# extio.net
KiCad netlist of a schematic drawn in EAGLE
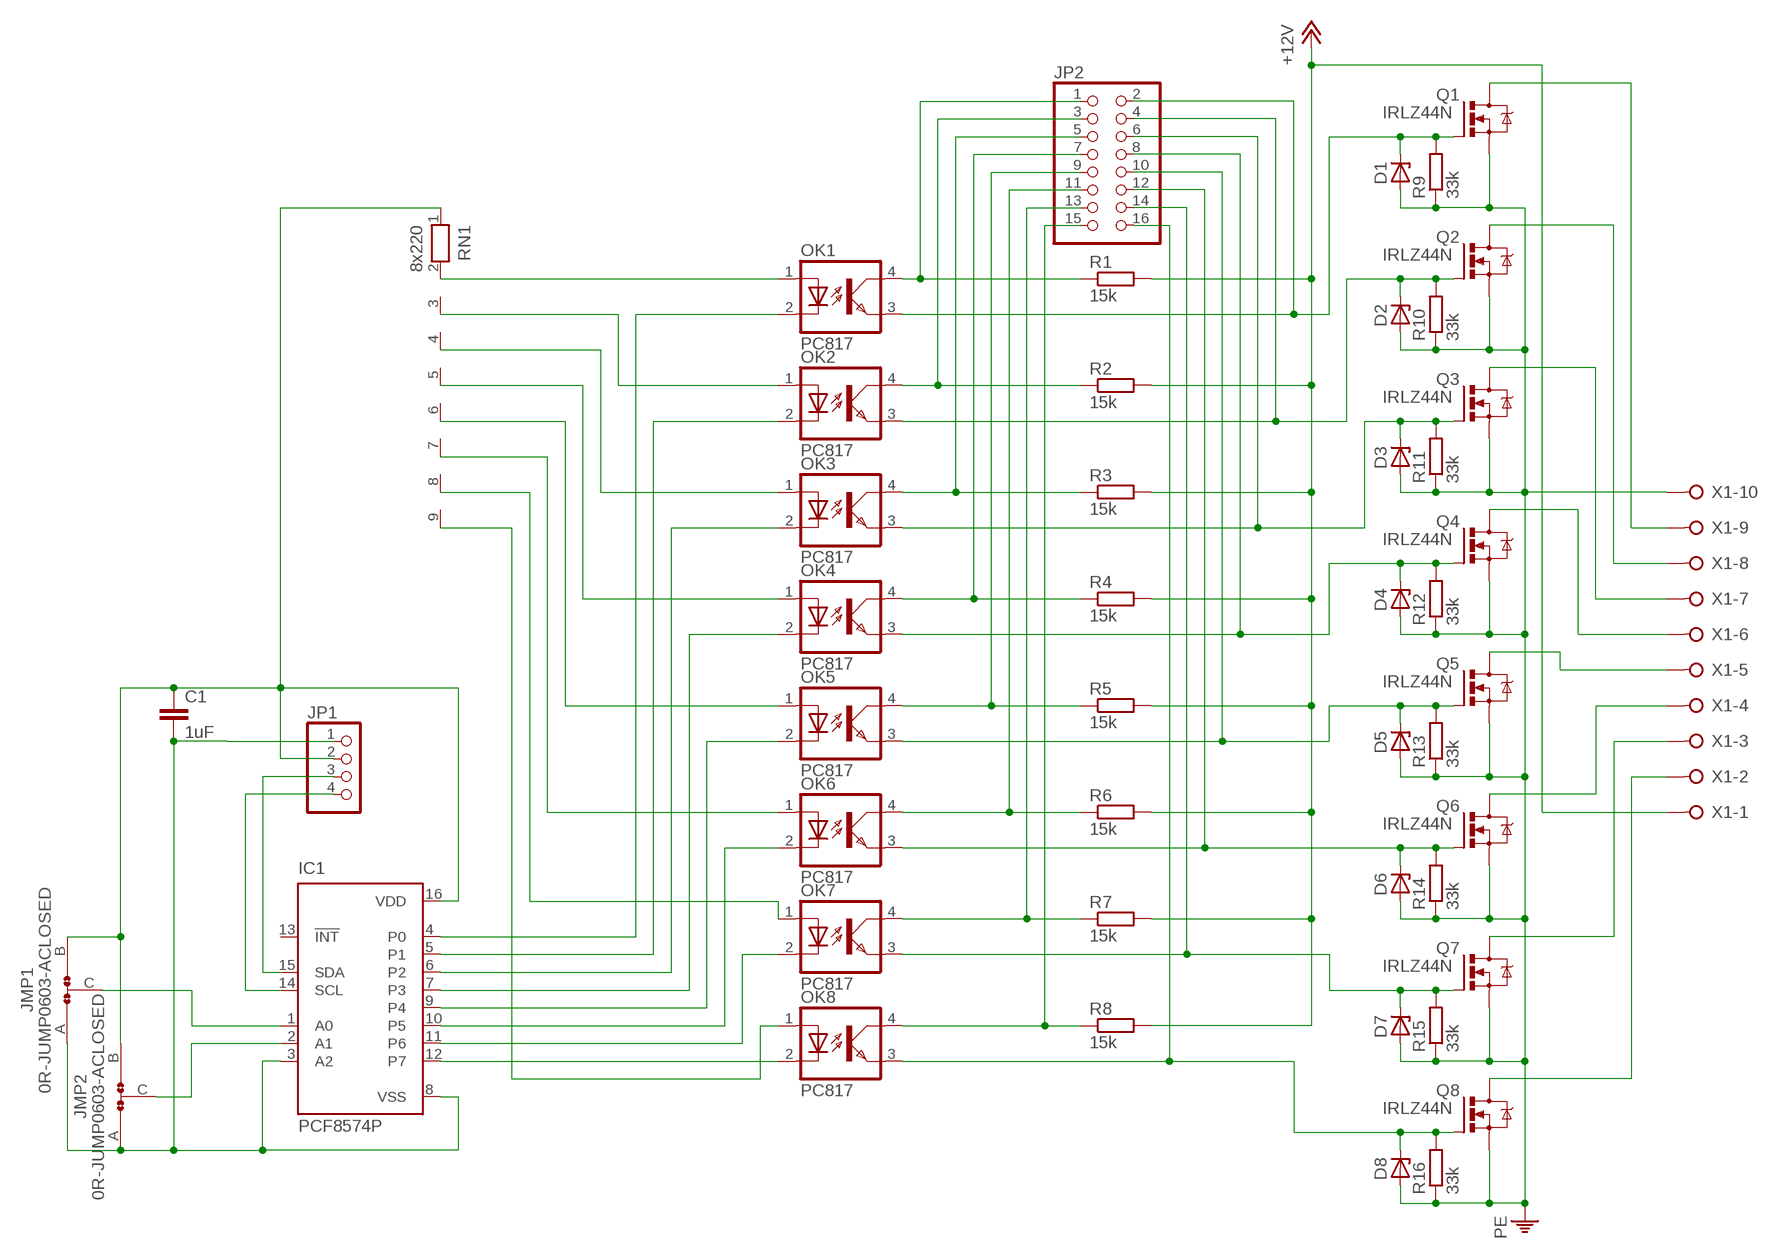
[diagram p0: schematic, sheet 1]

(export (version "E")
  (design (tool "Eeschema 10.0.6"))
  (components
    (comp (ref "C1")
      (value "1uF")
      (footprint "eagle-import:C0603")
      (libsource (lib "eagle-import") (part "C-EUC0603"))
    )
    (comp (ref "D1")
      (value "ZENER-DIODESOD80C")
      (footprint "eagle-import:SOD80C")
      (libsource (lib "eagle-import") (part "ZENER-DIODESOD80C"))
    )
    (comp (ref "D2")
      (value "ZENER-DIODESOD80C")
      (footprint "eagle-import:SOD80C")
      (libsource (lib "eagle-import") (part "ZENER-DIODESOD80C"))
    )
    (comp (ref "D3")
      (value "ZENER-DIODESOD80C")
      (footprint "eagle-import:SOD80C")
      (libsource (lib "eagle-import") (part "ZENER-DIODESOD80C"))
    )
    (comp (ref "D4")
      (value "ZENER-DIODESOD80C")
      (footprint "eagle-import:SOD80C")
      (libsource (lib "eagle-import") (part "ZENER-DIODESOD80C"))
    )
    (comp (ref "D5")
      (value "ZENER-DIODESOD80C")
      (footprint "eagle-import:SOD80C")
      (libsource (lib "eagle-import") (part "ZENER-DIODESOD80C"))
    )
    (comp (ref "D6")
      (value "ZENER-DIODESOD80C")
      (footprint "eagle-import:SOD80C")
      (libsource (lib "eagle-import") (part "ZENER-DIODESOD80C"))
    )
    (comp (ref "D7")
      (value "ZENER-DIODESOD80C")
      (footprint "eagle-import:SOD80C")
      (libsource (lib "eagle-import") (part "ZENER-DIODESOD80C"))
    )
    (comp (ref "D8")
      (value "ZENER-DIODESOD80C")
      (footprint "eagle-import:SOD80C")
      (libsource (lib "eagle-import") (part "ZENER-DIODESOD80C"))
    )
    (comp (ref "IC1")
      (value "PCF8574P")
      (footprint "eagle-import:DIL16")
      (fields (field (name "MPN") "PCF8574PN"))
      (libsource (lib "eagle-import") (part "PCF8574P"))
    )
    (comp (ref "JMP1")
      (value "0R-JUMP0603-ACLOSED")
      (footprint "eagle-import:JMP0603-ACLOSED")
      (libsource (lib "eagle-import") (part "0R-JUMP0603-ACLOSED"))
    )
    (comp (ref "JMP2")
      (value "0R-JUMP0603-ACLOSED")
      (footprint "eagle-import:JMP0603-ACLOSED")
      (libsource (lib "eagle-import") (part "0R-JUMP0603-ACLOSED"))
    )
    (comp (ref "JP1")
      (value "PINHD-1X4")
      (footprint "eagle-import:1X04")
      (libsource (lib "eagle-import") (part "PINHD-1X4"))
    )
    (comp (ref "JP2")
      (value "PINHD-2X8")
      (footprint "eagle-import:2X08")
      (libsource (lib "eagle-import") (part "PINHD-2X8"))
    )
    (comp (ref "OK1")
      (value "PC817")
      (footprint "eagle-import:DIL04")
      (fields (field (name "MPN") "PC817X4J000F"))
      (libsource (lib "eagle-import") (part "PC817"))
    )
    (comp (ref "OK2")
      (value "PC817")
      (footprint "eagle-import:DIL04")
      (fields (field (name "MPN") "PC817X4J000F"))
      (libsource (lib "eagle-import") (part "PC817"))
    )
    (comp (ref "OK3")
      (value "PC817")
      (footprint "eagle-import:DIL04")
      (fields (field (name "MPN") "PC817X4J000F"))
      (libsource (lib "eagle-import") (part "PC817"))
    )
    (comp (ref "OK4")
      (value "PC817")
      (footprint "eagle-import:DIL04")
      (fields (field (name "MPN") "PC817X4J000F"))
      (libsource (lib "eagle-import") (part "PC817"))
    )
    (comp (ref "OK5")
      (value "PC817")
      (footprint "eagle-import:DIL04")
      (fields (field (name "MPN") "PC817X4J000F"))
      (libsource (lib "eagle-import") (part "PC817"))
    )
    (comp (ref "OK6")
      (value "PC817")
      (footprint "eagle-import:DIL04")
      (fields (field (name "MPN") "PC817X4J000F"))
      (libsource (lib "eagle-import") (part "PC817"))
    )
    (comp (ref "OK7")
      (value "PC817")
      (footprint "eagle-import:DIL04")
      (fields (field (name "MPN") "PC817X4J000F"))
      (libsource (lib "eagle-import") (part "PC817"))
    )
    (comp (ref "OK8")
      (value "PC817")
      (footprint "eagle-import:DIL04")
      (fields (field (name "MPN") "PC817X4J000F"))
      (libsource (lib "eagle-import") (part "PC817"))
    )
    (comp (ref "Q1")
      (value "IRLZ44N")
      (footprint "eagle-import:TO220V")
      (libsource (lib "eagle-import") (part "IRLZ44N"))
    )
    (comp (ref "Q2")
      (value "IRLZ44N")
      (footprint "eagle-import:TO220V")
      (libsource (lib "eagle-import") (part "IRLZ44N"))
    )
    (comp (ref "Q3")
      (value "IRLZ44N")
      (footprint "eagle-import:TO220V")
      (libsource (lib "eagle-import") (part "IRLZ44N"))
    )
    (comp (ref "Q4")
      (value "IRLZ44N")
      (footprint "eagle-import:TO220V")
      (libsource (lib "eagle-import") (part "IRLZ44N"))
    )
    (comp (ref "Q5")
      (value "IRLZ44N")
      (footprint "eagle-import:TO220V")
      (libsource (lib "eagle-import") (part "IRLZ44N"))
    )
    (comp (ref "Q6")
      (value "IRLZ44N")
      (footprint "eagle-import:TO220V")
      (libsource (lib "eagle-import") (part "IRLZ44N"))
    )
    (comp (ref "Q7")
      (value "IRLZ44N")
      (footprint "eagle-import:TO220V")
      (libsource (lib "eagle-import") (part "IRLZ44N"))
    )
    (comp (ref "Q8")
      (value "IRLZ44N")
      (footprint "eagle-import:TO220V")
      (libsource (lib "eagle-import") (part "IRLZ44N"))
    )
    (comp (ref "R1")
      (value "15k")
      (footprint "eagle-import:R0603")
      (libsource (lib "eagle-import") (part "R-EU_R0603"))
    )
    (comp (ref "R2")
      (value "15k")
      (footprint "eagle-import:R0603")
      (libsource (lib "eagle-import") (part "R-EU_R0603"))
    )
    (comp (ref "R3")
      (value "15k")
      (footprint "eagle-import:R0603")
      (libsource (lib "eagle-import") (part "R-EU_R0603"))
    )
    (comp (ref "R4")
      (value "15k")
      (footprint "eagle-import:R0603")
      (libsource (lib "eagle-import") (part "R-EU_R0603"))
    )
    (comp (ref "R5")
      (value "15k")
      (footprint "eagle-import:R0603")
      (libsource (lib "eagle-import") (part "R-EU_R0603"))
    )
    (comp (ref "R6")
      (value "15k")
      (footprint "eagle-import:R0603")
      (libsource (lib "eagle-import") (part "R-EU_R0603"))
    )
    (comp (ref "R7")
      (value "15k")
      (footprint "eagle-import:R0603")
      (libsource (lib "eagle-import") (part "R-EU_R0603"))
    )
    (comp (ref "R8")
      (value "15k")
      (footprint "eagle-import:R0603")
      (libsource (lib "eagle-import") (part "R-EU_R0603"))
    )
    (comp (ref "R9")
      (value "33k")
      (footprint "eagle-import:R0603")
      (libsource (lib "eagle-import") (part "R-EU_R0603"))
    )
    (comp (ref "R10")
      (value "33k")
      (footprint "eagle-import:R0603")
      (libsource (lib "eagle-import") (part "R-EU_R0603"))
    )
    (comp (ref "R11")
      (value "33k")
      (footprint "eagle-import:R0603")
      (libsource (lib "eagle-import") (part "R-EU_R0603"))
    )
    (comp (ref "R12")
      (value "33k")
      (footprint "eagle-import:R0603")
      (libsource (lib "eagle-import") (part "R-EU_R0603"))
    )
    (comp (ref "R13")
      (value "33k")
      (footprint "eagle-import:R0603")
      (libsource (lib "eagle-import") (part "R-EU_R0603"))
    )
    (comp (ref "R14")
      (value "33k")
      (footprint "eagle-import:R0603")
      (libsource (lib "eagle-import") (part "R-EU_R0603"))
    )
    (comp (ref "R15")
      (value "33k")
      (footprint "eagle-import:R0603")
      (libsource (lib "eagle-import") (part "R-EU_R0603"))
    )
    (comp (ref "R16")
      (value "33k")
      (footprint "eagle-import:R0603")
      (libsource (lib "eagle-import") (part "R-EU_R0603"))
    )
    (comp (ref "RN1")
      (value "8x220")
      (footprint "eagle-import:RN-9")
      (libsource (lib "eagle-import") (part "RN08"))
    )
    (comp (ref "X1")
      (value "W237-10P")
      (footprint "eagle-import:W237-10P")
      (libsource (lib "eagle-import") (part "W237-10P"))
    )
  )
  (nets
    (net (code "1") (name "+12V") (class "Default")
      (node (ref "R1") (pin "2") (pinfunction "2_2") (pintype "passive"))
      (node (ref "R2") (pin "2") (pinfunction "2_2") (pintype "passive"))
      (node (ref "R3") (pin "2") (pinfunction "2_2") (pintype "passive"))
      (node (ref "R4") (pin "2") (pinfunction "2_2") (pintype "passive"))
      (node (ref "R5") (pin "2") (pinfunction "2_2") (pintype "passive"))
      (node (ref "R6") (pin "2") (pinfunction "2_2") (pintype "passive"))
      (node (ref "R7") (pin "2") (pinfunction "2_2") (pintype "passive"))
      (node (ref "R8") (pin "2") (pinfunction "2_2") (pintype "passive"))
      (node (ref "X1") (pin "1") (pinfunction "KL_1") (pintype "passive"))
    )
    (net (code "2") (name "Net-(IC1-A0)") (class "Default")
      (node (ref "IC1") (pin "1") (pinfunction "A0_1") (pintype "input"))
      (node (ref "JMP1") (pin "C") (pinfunction "C_C") (pintype "passive"))
    )
    (net (code "3") (name "Net-(IC1-A1)") (class "Default")
      (node (ref "IC1") (pin "2") (pinfunction "A1_2") (pintype "input"))
      (node (ref "JMP2") (pin "C") (pinfunction "C_C") (pintype "passive"))
    )
    (net (code "4") (name "Net-(IC1-A2)") (class "Default")
      (node (ref "C1") (pin "2") (pinfunction "2_2") (pintype "passive"))
      (node (ref "IC1") (pin "3") (pinfunction "A2_3") (pintype "input"))
      (node (ref "IC1") (pin "8") (pinfunction "VSS_8") (pintype "power_in"))
      (node (ref "JMP1") (pin "A") (pinfunction "A_A") (pintype "passive"))
      (node (ref "JMP2") (pin "A") (pinfunction "A_A") (pintype "passive"))
      (node (ref "JP1") (pin "1") (pinfunction "1_1") (pintype "passive"))
    )
    (net (code "5") (name "Net-(IC1-P0)") (class "Default")
      (node (ref "IC1") (pin "4") (pinfunction "P0_4") (pintype "bidirectional"))
      (node (ref "OK1") (pin "2") (pinfunction "C_2") (pintype "passive"))
    )
    (net (code "6") (name "Net-(IC1-P1)") (class "Default")
      (node (ref "IC1") (pin "5") (pinfunction "P1_5") (pintype "bidirectional"))
      (node (ref "OK2") (pin "2") (pinfunction "C_2") (pintype "passive"))
    )
    (net (code "7") (name "Net-(IC1-P2)") (class "Default")
      (node (ref "IC1") (pin "6") (pinfunction "P2_6") (pintype "bidirectional"))
      (node (ref "OK3") (pin "2") (pinfunction "C_2") (pintype "passive"))
    )
    (net (code "8") (name "Net-(IC1-P3)") (class "Default")
      (node (ref "IC1") (pin "7") (pinfunction "P3_7") (pintype "bidirectional"))
      (node (ref "OK4") (pin "2") (pinfunction "C_2") (pintype "passive"))
    )
    (net (code "9") (name "Net-(IC1-P4)") (class "Default")
      (node (ref "IC1") (pin "9") (pinfunction "P4_9") (pintype "bidirectional"))
      (node (ref "OK5") (pin "2") (pinfunction "C_2") (pintype "passive"))
    )
    (net (code "10") (name "Net-(IC1-P5)") (class "Default")
      (node (ref "IC1") (pin "10") (pinfunction "P5_10") (pintype "bidirectional"))
      (node (ref "OK6") (pin "2") (pinfunction "C_2") (pintype "passive"))
    )
    (net (code "11") (name "Net-(IC1-P6)") (class "Default")
      (node (ref "IC1") (pin "11") (pinfunction "P6_11") (pintype "bidirectional"))
      (node (ref "OK7") (pin "2") (pinfunction "C_2") (pintype "passive"))
    )
    (net (code "12") (name "Net-(IC1-P7)") (class "Default")
      (node (ref "IC1") (pin "12") (pinfunction "P7_12") (pintype "bidirectional"))
      (node (ref "OK8") (pin "2") (pinfunction "C_2") (pintype "passive"))
    )
    (net (code "13") (name "Net-(IC1-SCL)") (class "Default")
      (node (ref "IC1") (pin "14") (pinfunction "SCL_14") (pintype "input"))
      (node (ref "JP1") (pin "4") (pinfunction "4_4") (pintype "passive"))
    )
    (net (code "14") (name "Net-(IC1-SDA)") (class "Default")
      (node (ref "IC1") (pin "15") (pinfunction "SDA_15") (pintype "bidirectional"))
      (node (ref "JP1") (pin "3") (pinfunction "3_3") (pintype "passive"))
    )
    (net (code "15") (name "Net-(IC1-VDD)") (class "Default")
      (node (ref "C1") (pin "1") (pinfunction "1_1") (pintype "passive"))
      (node (ref "IC1") (pin "16") (pinfunction "VDD_16") (pintype "power_in"))
      (node (ref "JMP1") (pin "B") (pinfunction "B_B") (pintype "passive"))
      (node (ref "JMP2") (pin "B") (pinfunction "B_B") (pintype "passive"))
      (node (ref "JP1") (pin "2") (pinfunction "2_2") (pintype "passive"))
      (node (ref "RN1") (pin "1") (pinfunction "1_1") (pintype "passive"))
    )
    (net (code "16") (name "Net-(OK1-A)") (class "Default")
      (node (ref "OK1") (pin "1") (pinfunction "A_1") (pintype "passive"))
      (node (ref "RN1") (pin "2") (pinfunction "2_2") (pintype "passive"))
    )
    (net (code "17") (name "Net-(OK1-COL)") (class "Default")
      (node (ref "JP2") (pin "1") (pinfunction "1_1") (pintype "passive"))
      (node (ref "OK1") (pin "4") (pinfunction "COL_4") (pintype "passive"))
      (node (ref "R1") (pin "1") (pinfunction "1_1") (pintype "passive"))
    )
    (net (code "18") (name "Net-(OK1-EMIT)") (class "Default")
      (node (ref "D1") (pin "C") (pinfunction "C_C") (pintype "passive"))
      (node (ref "JP2") (pin "2") (pinfunction "2_2") (pintype "passive"))
      (node (ref "OK1") (pin "3") (pinfunction "EMIT_3") (pintype "passive"))
      (node (ref "Q1") (pin "1") (pinfunction "G_1") (pintype "passive"))
      (node (ref "R9") (pin "2") (pinfunction "2_2") (pintype "passive"))
    )
    (net (code "19") (name "Net-(OK2-A)") (class "Default")
      (node (ref "OK2") (pin "1") (pinfunction "A_1") (pintype "passive"))
      (node (ref "RN1") (pin "3") (pinfunction "3_3") (pintype "passive"))
    )
    (net (code "20") (name "Net-(OK2-COL)") (class "Default")
      (node (ref "JP2") (pin "3") (pinfunction "3_3") (pintype "passive"))
      (node (ref "OK2") (pin "4") (pinfunction "COL_4") (pintype "passive"))
      (node (ref "R2") (pin "1") (pinfunction "1_1") (pintype "passive"))
    )
    (net (code "21") (name "Net-(OK2-EMIT)") (class "Default")
      (node (ref "D2") (pin "C") (pinfunction "C_C") (pintype "passive"))
      (node (ref "JP2") (pin "4") (pinfunction "4_4") (pintype "passive"))
      (node (ref "OK2") (pin "3") (pinfunction "EMIT_3") (pintype "passive"))
      (node (ref "Q2") (pin "1") (pinfunction "G_1") (pintype "passive"))
      (node (ref "R10") (pin "2") (pinfunction "2_2") (pintype "passive"))
    )
    (net (code "22") (name "Net-(OK3-A)") (class "Default")
      (node (ref "OK3") (pin "1") (pinfunction "A_1") (pintype "passive"))
      (node (ref "RN1") (pin "4") (pinfunction "4_4") (pintype "passive"))
    )
    (net (code "23") (name "Net-(OK3-COL)") (class "Default")
      (node (ref "JP2") (pin "5") (pinfunction "5_5") (pintype "passive"))
      (node (ref "OK3") (pin "4") (pinfunction "COL_4") (pintype "passive"))
      (node (ref "R3") (pin "1") (pinfunction "1_1") (pintype "passive"))
    )
    (net (code "24") (name "Net-(OK3-EMIT)") (class "Default")
      (node (ref "D3") (pin "C") (pinfunction "C_C") (pintype "passive"))
      (node (ref "JP2") (pin "6") (pinfunction "6_6") (pintype "passive"))
      (node (ref "OK3") (pin "3") (pinfunction "EMIT_3") (pintype "passive"))
      (node (ref "Q3") (pin "1") (pinfunction "G_1") (pintype "passive"))
      (node (ref "R11") (pin "2") (pinfunction "2_2") (pintype "passive"))
    )
    (net (code "25") (name "Net-(OK4-A)") (class "Default")
      (node (ref "OK4") (pin "1") (pinfunction "A_1") (pintype "passive"))
      (node (ref "RN1") (pin "5") (pinfunction "5_5") (pintype "passive"))
    )
    (net (code "26") (name "Net-(OK4-COL)") (class "Default")
      (node (ref "JP2") (pin "7") (pinfunction "7_7") (pintype "passive"))
      (node (ref "OK4") (pin "4") (pinfunction "COL_4") (pintype "passive"))
      (node (ref "R4") (pin "1") (pinfunction "1_1") (pintype "passive"))
    )
    (net (code "27") (name "Net-(OK4-EMIT)") (class "Default")
      (node (ref "D4") (pin "C") (pinfunction "C_C") (pintype "passive"))
      (node (ref "JP2") (pin "8") (pinfunction "8_8") (pintype "passive"))
      (node (ref "OK4") (pin "3") (pinfunction "EMIT_3") (pintype "passive"))
      (node (ref "Q4") (pin "1") (pinfunction "G_1") (pintype "passive"))
      (node (ref "R12") (pin "2") (pinfunction "2_2") (pintype "passive"))
    )
    (net (code "28") (name "Net-(OK5-A)") (class "Default")
      (node (ref "OK5") (pin "1") (pinfunction "A_1") (pintype "passive"))
      (node (ref "RN1") (pin "6") (pinfunction "6_6") (pintype "passive"))
    )
    (net (code "29") (name "Net-(OK5-COL)") (class "Default")
      (node (ref "JP2") (pin "9") (pinfunction "9_9") (pintype "passive"))
      (node (ref "OK5") (pin "4") (pinfunction "COL_4") (pintype "passive"))
      (node (ref "R5") (pin "1") (pinfunction "1_1") (pintype "passive"))
    )
    (net (code "30") (name "Net-(OK5-EMIT)") (class "Default")
      (node (ref "D5") (pin "C") (pinfunction "C_C") (pintype "passive"))
      (node (ref "JP2") (pin "10") (pinfunction "10_10") (pintype "passive"))
      (node (ref "OK5") (pin "3") (pinfunction "EMIT_3") (pintype "passive"))
      (node (ref "Q5") (pin "1") (pinfunction "G_1") (pintype "passive"))
      (node (ref "R13") (pin "2") (pinfunction "2_2") (pintype "passive"))
    )
    (net (code "31") (name "Net-(OK6-A)") (class "Default")
      (node (ref "OK6") (pin "1") (pinfunction "A_1") (pintype "passive"))
      (node (ref "RN1") (pin "7") (pinfunction "7_7") (pintype "passive"))
    )
    (net (code "32") (name "Net-(OK6-COL)") (class "Default")
      (node (ref "JP2") (pin "11") (pinfunction "11_11") (pintype "passive"))
      (node (ref "OK6") (pin "4") (pinfunction "COL_4") (pintype "passive"))
      (node (ref "R6") (pin "1") (pinfunction "1_1") (pintype "passive"))
    )
    (net (code "33") (name "Net-(OK6-EMIT)") (class "Default")
      (node (ref "D6") (pin "C") (pinfunction "C_C") (pintype "passive"))
      (node (ref "JP2") (pin "12") (pinfunction "12_12") (pintype "passive"))
      (node (ref "OK6") (pin "3") (pinfunction "EMIT_3") (pintype "passive"))
      (node (ref "Q6") (pin "1") (pinfunction "G_1") (pintype "passive"))
      (node (ref "R14") (pin "2") (pinfunction "2_2") (pintype "passive"))
    )
    (net (code "34") (name "Net-(OK7-A)") (class "Default")
      (node (ref "OK7") (pin "1") (pinfunction "A_1") (pintype "passive"))
      (node (ref "RN1") (pin "8") (pinfunction "8_8") (pintype "passive"))
    )
    (net (code "35") (name "Net-(OK7-COL)") (class "Default")
      (node (ref "JP2") (pin "13") (pinfunction "13_13") (pintype "passive"))
      (node (ref "OK7") (pin "4") (pinfunction "COL_4") (pintype "passive"))
      (node (ref "R7") (pin "1") (pinfunction "1_1") (pintype "passive"))
    )
    (net (code "36") (name "Net-(OK7-EMIT)") (class "Default")
      (node (ref "D7") (pin "C") (pinfunction "C_C") (pintype "passive"))
      (node (ref "JP2") (pin "14") (pinfunction "14_14") (pintype "passive"))
      (node (ref "OK7") (pin "3") (pinfunction "EMIT_3") (pintype "passive"))
      (node (ref "Q7") (pin "1") (pinfunction "G_1") (pintype "passive"))
      (node (ref "R15") (pin "2") (pinfunction "2_2") (pintype "passive"))
    )
    (net (code "37") (name "Net-(OK8-A)") (class "Default")
      (node (ref "OK8") (pin "1") (pinfunction "A_1") (pintype "passive"))
      (node (ref "RN1") (pin "9") (pinfunction "9_9") (pintype "passive"))
    )
    (net (code "38") (name "Net-(OK8-COL)") (class "Default")
      (node (ref "JP2") (pin "15") (pinfunction "15_15") (pintype "passive"))
      (node (ref "OK8") (pin "4") (pinfunction "COL_4") (pintype "passive"))
      (node (ref "R8") (pin "1") (pinfunction "1_1") (pintype "passive"))
    )
    (net (code "39") (name "Net-(OK8-EMIT)") (class "Default")
      (node (ref "D8") (pin "C") (pinfunction "C_C") (pintype "passive"))
      (node (ref "JP2") (pin "16") (pinfunction "16_16") (pintype "passive"))
      (node (ref "OK8") (pin "3") (pinfunction "EMIT_3") (pintype "passive"))
      (node (ref "Q8") (pin "1") (pinfunction "G_1") (pintype "passive"))
      (node (ref "R16") (pin "2") (pinfunction "2_2") (pintype "passive"))
    )
    (net (code "40") (name "Net-(Q1-D)") (class "Default")
      (node (ref "Q1") (pin "2") (pinfunction "D_2") (pintype "passive"))
      (node (ref "X1") (pin "9") (pinfunction "KL_9") (pintype "passive"))
    )
    (net (code "41") (name "Net-(Q2-D)") (class "Default")
      (node (ref "Q2") (pin "2") (pinfunction "D_2") (pintype "passive"))
      (node (ref "X1") (pin "8") (pinfunction "KL_8") (pintype "passive"))
    )
    (net (code "42") (name "Net-(Q3-D)") (class "Default")
      (node (ref "Q3") (pin "2") (pinfunction "D_2") (pintype "passive"))
      (node (ref "X1") (pin "7") (pinfunction "KL_7") (pintype "passive"))
    )
    (net (code "43") (name "Net-(Q4-D)") (class "Default")
      (node (ref "Q4") (pin "2") (pinfunction "D_2") (pintype "passive"))
      (node (ref "X1") (pin "6") (pinfunction "KL_6") (pintype "passive"))
    )
    (net (code "44") (name "Net-(Q5-D)") (class "Default")
      (node (ref "Q5") (pin "2") (pinfunction "D_2") (pintype "passive"))
      (node (ref "X1") (pin "5") (pinfunction "KL_5") (pintype "passive"))
    )
    (net (code "45") (name "Net-(Q6-D)") (class "Default")
      (node (ref "Q6") (pin "2") (pinfunction "D_2") (pintype "passive"))
      (node (ref "X1") (pin "4") (pinfunction "KL_4") (pintype "passive"))
    )
    (net (code "46") (name "Net-(Q7-D)") (class "Default")
      (node (ref "Q7") (pin "2") (pinfunction "D_2") (pintype "passive"))
      (node (ref "X1") (pin "3") (pinfunction "KL_3") (pintype "passive"))
    )
    (net (code "47") (name "Net-(Q8-D)") (class "Default")
      (node (ref "Q8") (pin "2") (pinfunction "D_2") (pintype "passive"))
      (node (ref "X1") (pin "2") (pinfunction "KL_2") (pintype "passive"))
    )
    (net (code "48") (name "PE") (class "Default")
      (node (ref "D1") (pin "A") (pinfunction "A_A") (pintype "passive"))
      (node (ref "D2") (pin "A") (pinfunction "A_A") (pintype "passive"))
      (node (ref "D3") (pin "A") (pinfunction "A_A") (pintype "passive"))
      (node (ref "D4") (pin "A") (pinfunction "A_A") (pintype "passive"))
      (node (ref "D5") (pin "A") (pinfunction "A_A") (pintype "passive"))
      (node (ref "D6") (pin "A") (pinfunction "A_A") (pintype "passive"))
      (node (ref "D7") (pin "A") (pinfunction "A_A") (pintype "passive"))
      (node (ref "D8") (pin "A") (pinfunction "A_A") (pintype "passive"))
      (node (ref "Q1") (pin "3") (pinfunction "S_3") (pintype "passive"))
      (node (ref "Q2") (pin "3") (pinfunction "S_3") (pintype "passive"))
      (node (ref "Q3") (pin "3") (pinfunction "S_3") (pintype "passive"))
      (node (ref "Q4") (pin "3") (pinfunction "S_3") (pintype "passive"))
      (node (ref "Q5") (pin "3") (pinfunction "S_3") (pintype "passive"))
      (node (ref "Q6") (pin "3") (pinfunction "S_3") (pintype "passive"))
      (node (ref "Q7") (pin "3") (pinfunction "S_3") (pintype "passive"))
      (node (ref "Q8") (pin "3") (pinfunction "S_3") (pintype "passive"))
      (node (ref "R10") (pin "1") (pinfunction "1_1") (pintype "passive"))
      (node (ref "R11") (pin "1") (pinfunction "1_1") (pintype "passive"))
      (node (ref "R12") (pin "1") (pinfunction "1_1") (pintype "passive"))
      (node (ref "R13") (pin "1") (pinfunction "1_1") (pintype "passive"))
      (node (ref "R14") (pin "1") (pinfunction "1_1") (pintype "passive"))
      (node (ref "R15") (pin "1") (pinfunction "1_1") (pintype "passive"))
      (node (ref "R16") (pin "1") (pinfunction "1_1") (pintype "passive"))
      (node (ref "R9") (pin "1") (pinfunction "1_1") (pintype "passive"))
      (node (ref "X1") (pin "10") (pinfunction "KL_10") (pintype "passive"))
    )
    (net (code "49") (name "unconnected-(IC1-~{INT}-Pad13)") (class "Default")
      (node (ref "IC1") (pin "13") (pinfunction "~{INT}_13") (pintype "output"))
    )
  )
)
